# 05-Power.net
KiCad netlist of a schematic drawn in Altium Designer
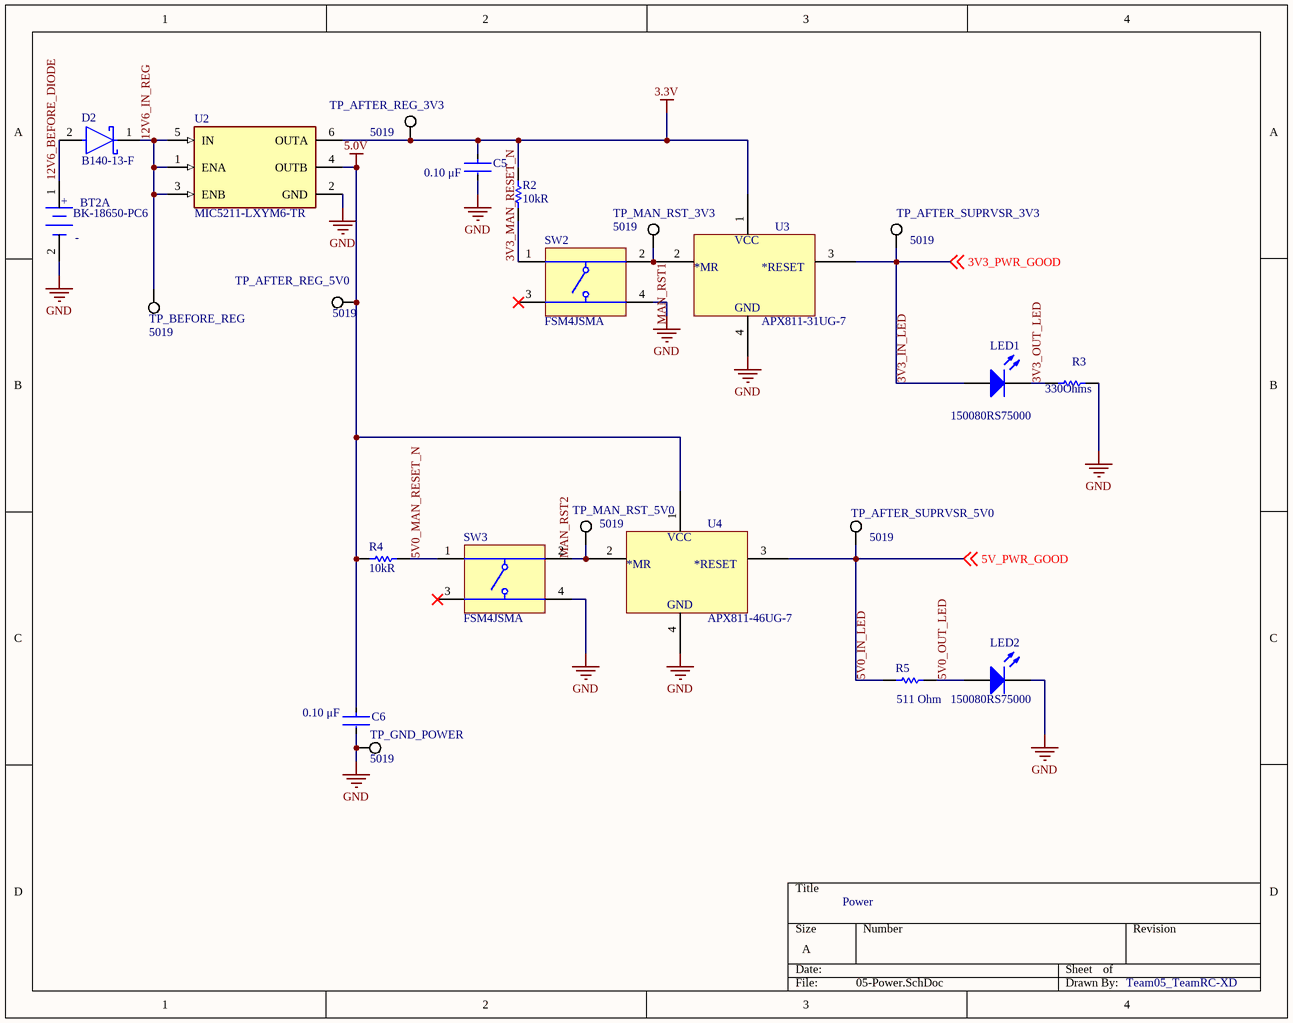
[diagram p0: 05-Power.SchDoc]

(export (version "E")
  (design (tool "Eeschema 10.0.6"))
  (components
    (comp (ref "BT2")
      (value "BK-18650-PC6")
      (footprint "FP-BK-18650-PC6-MFG")
      (description "BATT HOLDER 18650 3 CELL PC PIN")
      (fields
        (field (name "OCTOPART") "https://octopart.com/bk-18650-pc6-memory+protection+devices-19049091")
        (field (name "MANUFACTURER") "MPD (Memory Protection Devices)")
      )
      (libsource (lib "Altium Content Vault") (part "9e5c62ad4fe938611a07f7cfde2e9f3"))
    )
    (comp (ref "C5")
      (value "C0805C104K1RACAUTO")
      (footprint "FP-C0805C-DN-MFG")
      (description "CAP CER 0.1UF 100V X7R 0805")
      (fields
        (field (name "MANUFACTURER") "KEMET")
        (field (name "CAPACITANCE") "0.10 μF")
        (field (name "TOLERANCE") "0.1")
      )
      (libsource (lib "Altium Content Vault") (part "b4654b650e69147ec39a6b967a45e02"))
    )
    (comp (ref "C6")
      (value "C0805C104K1RACAUTO")
      (footprint "FP-C0805C-DN-MFG")
      (description "CAP CER 0.1UF 100V X7R 0805")
      (fields
        (field (name "MANUFACTURER") "KEMET")
        (field (name "CAPACITANCE") "0.10 μF")
        (field (name "TOLERANCE") "0.1")
      )
      (libsource (lib "Altium Content Vault") (part "b4654b650e69147ec39a6b967a45e02"))
    )
    (comp (ref "D2")
      (value "B140-13-F")
      (footprint "FP-SMA-MFG")
      (description "DIODE SCHOTTKY 40V 1A SMA")
      (fields (field (name "MANUFACTURER") "Diodes"))
      (libsource (lib "Altium Content Vault") (part "1d6ec82d83fb6aee721767c19dac4b9"))
    )
    (comp (ref "LED1")
      (value "150080RS75000")
      (footprint "0805_A")
      (description "SMD mono-color Chip LED, WL-SMCW, Red")
      (fields
        (field (name "MANUFACTURER") "Wuerth Elektronik")
        (field (name "MANUFACTURER PART NUMBER") "150080RS75000")
      )
      (libsource (lib "Altium Content Vault") (part "WE-LED_K1A2-2"))
    )
    (comp (ref "LED2")
      (value "150080RS75000")
      (footprint "0805_A")
      (description "SMD mono-color Chip LED, WL-SMCW, Red")
      (fields (field (name "MANUFACTURER") "Wuerth Elektronik"))
      (libsource (lib "Altium Content Vault") (part "WE-LED_K1A2-2"))
    )
    (comp (ref "R2")
      (value "RC0805FR-0710KL")
      (footprint "RESC2013X60X35NL10T20")
      (description "Chip Resistor, 10 KOhm, +/- 1%, 0.125 W, -55 to 155 degC, 0805 (2012 Metric), RoHS, Tape and Reel")
      (fields
        (field (name "MANUFACTURER") "Yageo")
        (field (name "RESISTANCE") "10kR")
        (field (name "TOLERANCE") "1%")
      )
      (libsource (lib "Altium Content Vault") (part "RES-2"))
    )
    (comp (ref "R3")
      (value "RC0805FR-07330RL")
      (footprint "RESC2013X60X35LL10T20")
      (description "Chip Resistor, 330 Ohm, +/- 1%, 125 mW, -55 to 155 degC, 0805 (2012 Metric), RoHS, Tape and Reel")
      (fields
        (field (name "MANUFACTURER") "Yageo")
        (field (name "TOLERANCE") "1%")
        (field (name "RESISTANCE") "330Ohms")
      )
      (libsource (lib "Altium Content Vault") (part "RES-2"))
    )
    (comp (ref "R4")
      (value "RC0805FR-0710KL")
      (footprint "RESC2013X60X35NL10T20")
      (description "Chip Resistor, 10 KOhm, +/- 1%, 0.125 W, -55 to 155 degC, 0805 (2012 Metric), RoHS, Tape and Reel")
      (fields
        (field (name "MANUFACTURER") "Yageo")
        (field (name "RESISTANCE") "10kR")
        (field (name "TOLERANCE") "1%")
      )
      (libsource (lib "Altium Content Vault") (part "RES-2"))
    )
    (comp (ref "R5")
      (value "ERJ-6ENF5110V")
      (footprint "RESC2013X70X40ML20T20")
      (description "511 Ohm Resisitor")
      (fields
        (field (name "MANUFACTURER") "Panasonic")
        (field (name "RESISTANCE") "511 Ohm")
        (field (name "TOLERANCE") "1%")
      )
      (libsource (lib "Altium Content Vault") (part "RES"))
    )
    (comp (ref "SW2")
      (value "FSM4JSMA")
      (footprint "TECO-FSM4JSMA_V")
      (description "Swicth, SPST, 24 V, -35 to 85 degC, 4-Pin SMD, RoHS, Tape and Reel")
      (fields (field (name "MANUFACTURER") "TE Connectivity"))
      (libsource (lib "Altium Content Vault") (part "SW-SPST-4_A"))
    )
    (comp (ref "SW3")
      (value "FSM4JSMA")
      (footprint "TECO-FSM4JSMA_V")
      (description "Swicth, SPST, 24 V, -35 to 85 degC, 4-Pin SMD, RoHS, Tape and Reel")
      (fields (field (name "MANUFACTURER") "TE Connectivity"))
      (libsource (lib "Altium Content Vault") (part "SW-SPST-4_A"))
    )
    (comp (ref "TP_AFTER_REG_3V3")
      (value "5019")
      (footprint "KSTN-5019_V")
      (description "Test Point, 1 Position SMD, RoHS, Tape and Reel")
      (fields (field (name "MANUFACTURER") "Keystone Electronics"))
      (libsource (lib "Altium Content Vault") (part "TESTPOINT_WHITE"))
    )
    (comp (ref "TP_AFTER_REG_5V0")
      (value "5019")
      (footprint "KSTN-5019_V")
      (description "Test Point, 1 Position SMD, RoHS, Tape and Reel")
      (fields (field (name "MANUFACTURER") "Keystone Electronics"))
      (libsource (lib "Altium Content Vault") (part "TESTPOINT_WHITE"))
    )
    (comp (ref "TP_AFTER_SUPRVSR_3V3")
      (value "5019")
      (footprint "KSTN-5019_V")
      (description "Test Point, 1 Position SMD, RoHS, Tape and Reel")
      (fields (field (name "MANUFACTURER") "Keystone Electronics"))
      (libsource (lib "Altium Content Vault") (part "TESTPOINT_WHITE"))
    )
    (comp (ref "TP_AFTER_SUPRVSR_5V0")
      (value "5019")
      (footprint "KSTN-5019_V")
      (description "Test Point, 1 Position SMD, RoHS, Tape and Reel")
      (fields (field (name "MANUFACTURER") "Keystone Electronics"))
      (libsource (lib "Altium Content Vault") (part "TESTPOINT_WHITE"))
    )
    (comp (ref "TP_BEFORE_REG")
      (value "5019")
      (footprint "KSTN-5019_V")
      (description "Test Point, 1 Position SMD, RoHS, Tape and Reel")
      (fields (field (name "MANUFACTURER") "Keystone Electronics"))
      (libsource (lib "Altium Content Vault") (part "TESTPOINT_WHITE"))
    )
    (comp (ref "TP_GND_POWER")
      (value "5019")
      (footprint "KSTN-5019_V")
      (description "Test Point, 1 Position SMD, RoHS, Tape and Reel")
      (fields (field (name "MANUFACTURER") "Keystone Electronics"))
      (libsource (lib "Altium Content Vault") (part "TESTPOINT_WHITE"))
    )
    (comp (ref "TP_MAN_RST_3V3")
      (value "5019")
      (footprint "KSTN-5019_V")
      (description "Test Point, 1 Position SMD, RoHS, Tape and Reel")
      (fields (field (name "MANUFACTURER") "Keystone Electronics"))
      (libsource (lib "Altium Content Vault") (part "TESTPOINT_WHITE"))
    )
    (comp (ref "TP_MAN_RST_5V0")
      (value "5019")
      (footprint "KSTN-5019_V")
      (description "Test Point, 1 Position SMD, RoHS, Tape and Reel")
      (fields (field (name "MANUFACTURER") "Keystone Electronics"))
      (libsource (lib "Altium Content Vault") (part "TESTPOINT_WHITE"))
    )
    (comp (ref "U2")
      (value "MIC5211-LXYM6-TR")
      (footprint "FP-SOT23-6LD-PL-1-MFG")
      (description "IC REG LINEAR 3.3V/5V SOT23-6")
      (fields (field (name "MANUFACTURER") "Microchip"))
      (libsource (lib "Altium Content Vault") (part "5117730c73b681657c483658370bd1f"))
    )
    (comp (ref "U3")
      (value "APX811-31UG-7")
      (footprint "SOT143")
      (description "IC SUPERVISOR 3.08V SOT143-4")
      (fields (field (name "MANUFACTURER") "Diodes"))
      (libsource (lib "APX811-31UG-7") (part "APX811-31UG-7"))
    )
    (comp (ref "U4")
      (value "APX811-46UG-7")
      (footprint "SOT143")
      (description "4-Pin Microprocessor Supervisor With Manual Reset, 5.5V, 20µA, -40°C to 85°C")
      (fields (field (name "MANUFACTURER") "Diodes"))
      (libsource (lib "APX811-31UG-7") (part "APX811-46UG-7"))
    )
  )
  (nets
    (net (code "1") (name "/3V3_MAN_RESET_N") (class "Default")
      (node (ref "R2") (pin "1") (pinfunction "1_1") (pintype "passive"))
      (node (ref "SW2") (pin "1") (pinfunction "1_1") (pintype "passive"))
    )
    (net (code "2") (name "/3V3_OUT_LED") (class "Default")
      (node (ref "LED1") (pin "1") (pinfunction "K_1") (pintype "passive"))
      (node (ref "R3") (pin "1") (pinfunction "1_1") (pintype "passive"))
    )
    (net (code "3") (name "/5V0_MAN_RESET_N") (class "Default")
      (node (ref "R4") (pin "1") (pinfunction "1_1") (pintype "passive"))
      (node (ref "SW3") (pin "1") (pinfunction "1_1") (pintype "passive"))
    )
    (net (code "4") (name "/5V0_OUT_LED") (class "Default")
      (node (ref "LED2") (pin "2") (pinfunction "A_2") (pintype "passive"))
      (node (ref "R5") (pin "2") (pinfunction "2_2") (pintype "passive"))
    )
    (net (code "5") (name "/12V6_BEFORE_DIODE") (class "Default")
      (node (ref "BT2") (pin "1") (pinfunction "1_+_1") (pintype "passive"))
      (node (ref "D2") (pin "2") (pinfunction "A_2") (pintype "passive"))
    )
    (net (code "6") (name "/12V6_IN_REG") (class "Default")
      (node (ref "D2") (pin "1") (pinfunction "C_1") (pintype "passive"))
      (node (ref "TP_BEFORE_REG") (pin "1") (pinfunction "1_1") (pintype "passive"))
      (node (ref "U2") (pin "1") (pinfunction "ENA_1") (pintype "input"))
      (node (ref "U2") (pin "3") (pinfunction "ENB_3") (pintype "input"))
      (node (ref "U2") (pin "5") (pinfunction "IN_5") (pintype "input"))
    )
    (net (code "7") (name "/MAN_RST1") (class "Default")
      (node (ref "SW2") (pin "2") (pinfunction "2_2") (pintype "passive"))
      (node (ref "TP_MAN_RST_3V3") (pin "1") (pinfunction "1_1") (pintype "passive"))
      (node (ref "U3") (pin "2") (pinfunction "2_2") (pintype "passive"))
    )
    (net (code "8") (name "/MAN_RST2") (class "Default")
      (node (ref "SW3") (pin "2") (pinfunction "2_2") (pintype "passive"))
      (node (ref "TP_MAN_RST_5V0") (pin "1") (pinfunction "1_1") (pintype "passive"))
      (node (ref "U4") (pin "2") (pinfunction "2_2") (pintype "passive"))
    )
    (net (code "9") (name "3.3V") (class "Default")
      (node (ref "C5") (pin "1") (pinfunction "1_1") (pintype "passive"))
      (node (ref "R2") (pin "2") (pinfunction "2_2") (pintype "passive"))
      (node (ref "TP_AFTER_REG_3V3") (pin "1") (pinfunction "1_1") (pintype "passive"))
      (node (ref "U2") (pin "6") (pinfunction "OUTA_6") (pintype "passive"))
      (node (ref "U3") (pin "1") (pinfunction "1_1") (pintype "passive"))
    )
    (net (code "10") (name "3V3_PWR_GOOD") (class "Default")
      (node (ref "LED1") (pin "2") (pinfunction "A_2") (pintype "passive"))
      (node (ref "TP_AFTER_SUPRVSR_3V3") (pin "1") (pinfunction "1_1") (pintype "passive"))
      (node (ref "U3") (pin "3") (pinfunction "3_3") (pintype "passive"))
    )
    (net (code "11") (name "5.0V") (class "Default")
      (node (ref "C6") (pin "1") (pinfunction "1_1") (pintype "passive"))
      (node (ref "R4") (pin "2") (pinfunction "2_2") (pintype "passive"))
      (node (ref "TP_AFTER_REG_5V0") (pin "1") (pinfunction "1_1") (pintype "passive"))
      (node (ref "U2") (pin "4") (pinfunction "OUTB_4") (pintype "passive"))
      (node (ref "U4") (pin "1") (pinfunction "1_1") (pintype "passive"))
    )
    (net (code "12") (name "5V_PWR_GOOD") (class "Default")
      (node (ref "R5") (pin "1") (pinfunction "1_1") (pintype "passive"))
      (node (ref "TP_AFTER_SUPRVSR_5V0") (pin "1") (pinfunction "1_1") (pintype "passive"))
      (node (ref "U4") (pin "3") (pinfunction "3_3") (pintype "passive"))
    )
    (net (code "13") (name "GND") (class "Default")
      (node (ref "BT2") (pin "2") (pinfunction "1_-_2") (pintype "passive"))
      (node (ref "C5") (pin "2") (pinfunction "2_2") (pintype "passive"))
      (node (ref "C6") (pin "2") (pinfunction "2_2") (pintype "passive"))
      (node (ref "LED2") (pin "1") (pinfunction "K_1") (pintype "passive"))
      (node (ref "R3") (pin "2") (pinfunction "2_2") (pintype "passive"))
      (node (ref "SW2") (pin "4") (pinfunction "4_4") (pintype "passive"))
      (node (ref "SW3") (pin "4") (pinfunction "4_4") (pintype "passive"))
      (node (ref "TP_GND_POWER") (pin "1") (pinfunction "1_1") (pintype "passive"))
      (node (ref "U2") (pin "2") (pinfunction "GND_2") (pintype "power_in"))
      (node (ref "U3") (pin "4") (pinfunction "4_4") (pintype "passive"))
      (node (ref "U4") (pin "4") (pinfunction "4_4") (pintype "passive"))
    )
    (net (code "14") (name "unconnected-(SW2-Pad3)") (class "Default")
      (node (ref "SW2") (pin "3") (pinfunction "3_3") (pintype "passive+no_connect"))
    )
    (net (code "15") (name "unconnected-(SW3-Pad3)") (class "Default")
      (node (ref "SW3") (pin "3") (pinfunction "3_3") (pintype "passive+no_connect"))
    )
  )
)
